# ATEM_GPI-Tally_Breakout_Board.net
KiCad netlist of a schematic drawn in EAGLE
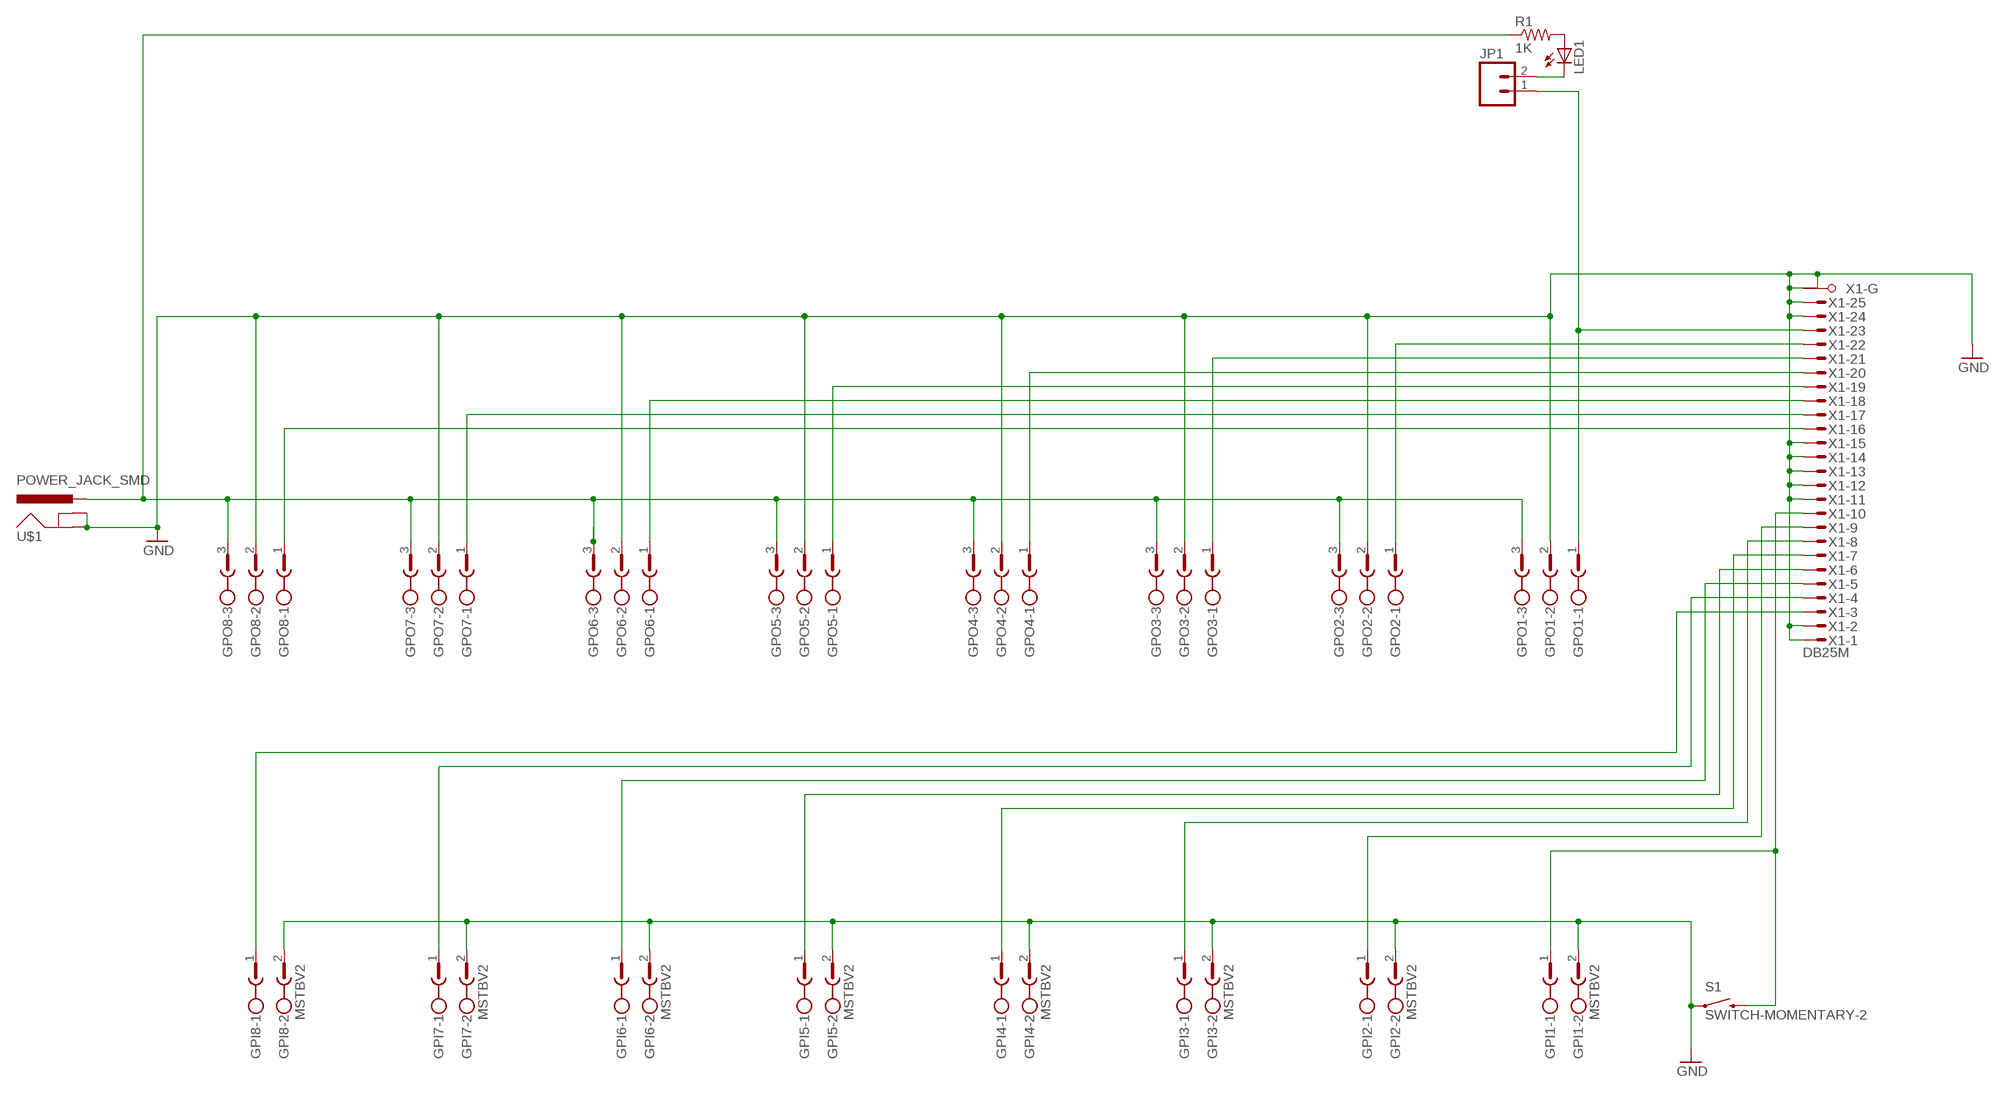
[diagram p0: schematic, sheet 1]

(export (version "E")
  (design (tool "Eeschema 10.0.6"))
  (components
    (comp (ref "GPI1")
      (value "MSTBV2")
      (footprint "eagle-import:MSTBV2")
      (fields
        (field (name "MPN") "MSTBV 2,5/2-GF-5.08")
        (field (name "MPN_1") "MSTBV 2,5/2-GF-5.08")
        (field (name "OC_FARNELL") "1792792")
        (field (name "OC_NEWARK") "69R9845")
      )
      (libsource (lib "eagle-import") (part "MSTBV2"))
    )
    (comp (ref "GPI2")
      (value "MSTBV2")
      (footprint "eagle-import:MSTBV2")
      (fields
        (field (name "MPN") "MSTBV 2,5/2-GF-5.08")
        (field (name "MPN_1") "MSTBV 2,5/2-GF-5.08")
        (field (name "OC_FARNELL") "1792792")
        (field (name "OC_NEWARK") "69R9845")
      )
      (libsource (lib "eagle-import") (part "MSTBV2"))
    )
    (comp (ref "GPI3")
      (value "MSTBV2")
      (footprint "eagle-import:MSTBV2")
      (fields
        (field (name "MPN") "MSTBV 2,5/2-GF-5.08")
        (field (name "MPN_1") "MSTBV 2,5/2-GF-5.08")
        (field (name "OC_FARNELL") "1792792")
        (field (name "OC_NEWARK") "69R9845")
      )
      (libsource (lib "eagle-import") (part "MSTBV2"))
    )
    (comp (ref "GPI4")
      (value "MSTBV2")
      (footprint "eagle-import:MSTBV2")
      (fields
        (field (name "MPN") "MSTBV 2,5/2-GF-5.08")
        (field (name "MPN_1") "MSTBV 2,5/2-GF-5.08")
        (field (name "OC_FARNELL") "1792792")
        (field (name "OC_NEWARK") "69R9845")
      )
      (libsource (lib "eagle-import") (part "MSTBV2"))
    )
    (comp (ref "GPI5")
      (value "MSTBV2")
      (footprint "eagle-import:MSTBV2")
      (fields
        (field (name "MPN") "MSTBV 2,5/2-GF-5.08")
        (field (name "MPN_1") "MSTBV 2,5/2-GF-5.08")
        (field (name "OC_FARNELL") "1792792")
        (field (name "OC_NEWARK") "69R9845")
      )
      (libsource (lib "eagle-import") (part "MSTBV2"))
    )
    (comp (ref "GPI6")
      (value "MSTBV2")
      (footprint "eagle-import:MSTBV2")
      (fields
        (field (name "MPN") "MSTBV 2,5/2-GF-5.08")
        (field (name "MPN_1") "MSTBV 2,5/2-GF-5.08")
        (field (name "OC_FARNELL") "1792792")
        (field (name "OC_NEWARK") "69R9845")
      )
      (libsource (lib "eagle-import") (part "MSTBV2"))
    )
    (comp (ref "GPI7")
      (value "MSTBV2")
      (footprint "eagle-import:MSTBV2")
      (fields
        (field (name "MPN") "MSTBV 2,5/2-GF-5.08")
        (field (name "MPN_1") "MSTBV 2,5/2-GF-5.08")
        (field (name "OC_FARNELL") "1792792")
        (field (name "OC_NEWARK") "69R9845")
      )
      (libsource (lib "eagle-import") (part "MSTBV2"))
    )
    (comp (ref "GPI8")
      (value "MSTBV2")
      (footprint "eagle-import:MSTBV2")
      (fields
        (field (name "MPN") "MSTBV 2,5/2-GF-5.08")
        (field (name "MPN_1") "MSTBV 2,5/2-GF-5.08")
        (field (name "OC_FARNELL") "1792792")
        (field (name "OC_NEWARK") "69R9845")
      )
      (libsource (lib "eagle-import") (part "MSTBV2"))
    )
    (comp (ref "GPO1")
      (value "CON1")
      (footprint "eagle-import:MSTBV3")
      (fields (field (name "MPN") "MSTBV 2,5/3-GF-5.08"))
      (libsource (lib "eagle-import") (part "MSTBV3"))
    )
    (comp (ref "GPO2")
      (value "CON1")
      (footprint "eagle-import:MSTBV3")
      (fields (field (name "MPN") "MSTBV 2,5/3-GF-5.08"))
      (libsource (lib "eagle-import") (part "MSTBV3"))
    )
    (comp (ref "GPO3")
      (value "CON1")
      (footprint "eagle-import:MSTBV3")
      (fields (field (name "MPN") "MSTBV 2,5/3-GF-5.08"))
      (libsource (lib "eagle-import") (part "MSTBV3"))
    )
    (comp (ref "GPO4")
      (value "CON1")
      (footprint "eagle-import:MSTBV3")
      (fields (field (name "MPN") "MSTBV 2,5/3-GF-5.08"))
      (libsource (lib "eagle-import") (part "MSTBV3"))
    )
    (comp (ref "GPO5")
      (value "CON1")
      (footprint "eagle-import:MSTBV3")
      (fields (field (name "MPN") "MSTBV 2,5/3-GF-5.08"))
      (libsource (lib "eagle-import") (part "MSTBV3"))
    )
    (comp (ref "GPO6")
      (value "CON1")
      (footprint "eagle-import:MSTBV3")
      (fields (field (name "MPN") "MSTBV 2,5/3-GF-5.08"))
      (libsource (lib "eagle-import") (part "MSTBV3"))
    )
    (comp (ref "GPO7")
      (value "CON1")
      (footprint "eagle-import:MSTBV3")
      (fields (field (name "MPN") "MSTBV 2,5/3-GF-5.08"))
      (libsource (lib "eagle-import") (part "MSTBV3"))
    )
    (comp (ref "GPO8")
      (value "CON1")
      (footprint "eagle-import:MSTBV3")
      (fields (field (name "MPN") "MSTBV 2,5/3-GF-5.08"))
      (libsource (lib "eagle-import") (part "MSTBV3"))
    )
    (comp (ref "JP1")
      (value "M02LOCK")
      (footprint "eagle-import:1X02_LOCK")
      (libsource (lib "eagle-import") (part "M02LOCK"))
    )
    (comp (ref "LED1")
      (value "LED5MM")
      (footprint "eagle-import:LED5MM")
      (libsource (lib "eagle-import") (part "LED5MM"))
    )
    (comp (ref "R1")
      (value "1K")
      (footprint "eagle-import:AXIAL-0.4")
      (libsource (lib "eagle-import") (part "RESISTORPTH-1/4W"))
    )
    (comp (ref "S1")
      (value "SWITCH-MOMENTARY-2")
      (footprint "eagle-import:TACTILE_SWITCH_TALL")
      (libsource (lib "eagle-import") (part "SWITCH-MOMENTARY-2"))
    )
    (comp (ref "U$1")
      (value "POWER_JACK_SMD")
      (footprint "eagle-import:POWER_JACK_SMD")
      (libsource (lib "eagle-import") (part "POWER_JACK_SMD"))
    )
    (comp (ref "X1")
      (value "DB25M")
      (footprint "eagle-import:M25HP")
      (libsource (lib "eagle-import") (part "M25HPS"))
    )
  )
  (nets
    (net (code "1") (name "GND") (class "Default")
      (node (ref "GPI1") (pin "2") (pinfunction "1_2") (pintype "passive"))
      (node (ref "GPI2") (pin "2") (pinfunction "1_2") (pintype "passive"))
      (node (ref "GPI3") (pin "2") (pinfunction "1_2") (pintype "passive"))
      (node (ref "GPI4") (pin "2") (pinfunction "1_2") (pintype "passive"))
      (node (ref "GPI5") (pin "2") (pinfunction "1_2") (pintype "passive"))
      (node (ref "GPI6") (pin "2") (pinfunction "1_2") (pintype "passive"))
      (node (ref "GPI7") (pin "2") (pinfunction "1_2") (pintype "passive"))
      (node (ref "GPI8") (pin "2") (pinfunction "1_2") (pintype "passive"))
      (node (ref "GPO1") (pin "2") (pinfunction "1_2") (pintype "passive"))
      (node (ref "GPO2") (pin "2") (pinfunction "1_2") (pintype "passive"))
      (node (ref "GPO3") (pin "2") (pinfunction "1_2") (pintype "passive"))
      (node (ref "GPO4") (pin "2") (pinfunction "1_2") (pintype "passive"))
      (node (ref "GPO5") (pin "2") (pinfunction "1_2") (pintype "passive"))
      (node (ref "GPO6") (pin "2") (pinfunction "1_2") (pintype "passive"))
      (node (ref "GPO7") (pin "2") (pinfunction "1_2") (pintype "passive"))
      (node (ref "GPO8") (pin "2") (pinfunction "1_2") (pintype "passive"))
      (node (ref "S1") (pin "A2") (pinfunction "1_A2") (pintype "passive"))
      (node (ref "U$1") (pin "GND") (pinfunction "GND_GND") (pintype "bidirectional"))
      (node (ref "U$1") (pin "SHUNT") (pinfunction "GNDBREAK_SHUNT") (pintype "bidirectional"))
      (node (ref "X1") (pin "1") (pinfunction "M_1") (pintype "passive"))
      (node (ref "X1") (pin "11") (pinfunction "M_11") (pintype "passive"))
      (node (ref "X1") (pin "12") (pinfunction "M_12") (pintype "passive"))
      (node (ref "X1") (pin "13") (pinfunction "M_13") (pintype "passive"))
      (node (ref "X1") (pin "14") (pinfunction "M_14") (pintype "passive"))
      (node (ref "X1") (pin "15") (pinfunction "M_15") (pintype "passive"))
      (node (ref "X1") (pin "2") (pinfunction "M_2") (pintype "passive"))
      (node (ref "X1") (pin "24") (pinfunction "M_24") (pintype "passive"))
      (node (ref "X1") (pin "25") (pinfunction "M_25") (pintype "passive"))
      (node (ref "X1") (pin "G1") (pinfunction "G1_G1") (pintype "passive"))
      (node (ref "X1") (pin "G2") (pinfunction "G2_G2") (pintype "passive"))
    )
    (net (code "2") (name "Net-(GPO1C-1)") (class "Default")
      (node (ref "GPO1") (pin "3") (pinfunction "1_3") (pintype "passive"))
      (node (ref "GPO2") (pin "3") (pinfunction "1_3") (pintype "passive"))
      (node (ref "GPO3") (pin "3") (pinfunction "1_3") (pintype "passive"))
      (node (ref "GPO4") (pin "3") (pinfunction "1_3") (pintype "passive"))
      (node (ref "GPO5") (pin "3") (pinfunction "1_3") (pintype "passive"))
      (node (ref "GPO6") (pin "3") (pinfunction "1_3") (pintype "passive"))
      (node (ref "GPO7") (pin "3") (pinfunction "1_3") (pintype "passive"))
      (node (ref "GPO8") (pin "3") (pinfunction "1_3") (pintype "passive"))
      (node (ref "R1") (pin "P$1") (pinfunction "1_P$1") (pintype "passive"))
      (node (ref "U$1") (pin "PWR") (pinfunction "PWR_PWR") (pintype "bidirectional"))
    )
    (net (code "3") (name "Net-(LED1-C)") (class "Default")
      (node (ref "JP1") (pin "2") (pinfunction "2_2") (pintype "passive"))
      (node (ref "LED1") (pin "K") (pinfunction "C_K") (pintype "passive"))
    )
    (net (code "4") (name "Net-(R1-2)") (class "Default")
      (node (ref "LED1") (pin "A") (pinfunction "A_A") (pintype "passive"))
      (node (ref "R1") (pin "P$2") (pinfunction "2_P$2") (pintype "passive"))
    )
    (net (code "5") (name "Net-(S1-2)") (class "Default")
      (node (ref "GPI1") (pin "1") (pinfunction "1_1") (pintype "passive"))
      (node (ref "S1") (pin "B2") (pinfunction "2_B2") (pintype "passive"))
      (node (ref "X1") (pin "10") (pinfunction "M_10") (pintype "passive"))
    )
    (net (code "6") (name "Net-(X1H-M)") (class "Default")
      (node (ref "GPO8") (pin "1") (pinfunction "1_1") (pintype "passive"))
      (node (ref "X1") (pin "16") (pinfunction "M_16") (pintype "passive"))
    )
    (net (code "7") (name "Net-(X1I-M)") (class "Default")
      (node (ref "GPO7") (pin "1") (pinfunction "1_1") (pintype "passive"))
      (node (ref "X1") (pin "17") (pinfunction "M_17") (pintype "passive"))
    )
    (net (code "8") (name "Net-(X1J-M)") (class "Default")
      (node (ref "GPO6") (pin "1") (pinfunction "1_1") (pintype "passive"))
      (node (ref "X1") (pin "18") (pinfunction "M_18") (pintype "passive"))
    )
    (net (code "9") (name "Net-(X1K-M)") (class "Default")
      (node (ref "GPO5") (pin "1") (pinfunction "1_1") (pintype "passive"))
      (node (ref "X1") (pin "19") (pinfunction "M_19") (pintype "passive"))
    )
    (net (code "10") (name "Net-(X1M-M)") (class "Default")
      (node (ref "GPO4") (pin "1") (pinfunction "1_1") (pintype "passive"))
      (node (ref "X1") (pin "20") (pinfunction "M_20") (pintype "passive"))
    )
    (net (code "11") (name "Net-(X1N-M)") (class "Default")
      (node (ref "GPO3") (pin "1") (pinfunction "1_1") (pintype "passive"))
      (node (ref "X1") (pin "21") (pinfunction "M_21") (pintype "passive"))
    )
    (net (code "12") (name "Net-(X1O-M)") (class "Default")
      (node (ref "GPO2") (pin "1") (pinfunction "1_1") (pintype "passive"))
      (node (ref "X1") (pin "22") (pinfunction "M_22") (pintype "passive"))
    )
    (net (code "13") (name "Net-(X1P-M)") (class "Default")
      (node (ref "GPO1") (pin "1") (pinfunction "1_1") (pintype "passive"))
      (node (ref "JP1") (pin "1") (pinfunction "1_1") (pintype "passive"))
      (node (ref "X1") (pin "23") (pinfunction "M_23") (pintype "passive"))
    )
    (net (code "14") (name "Net-(X1S-M)") (class "Default")
      (node (ref "GPI8") (pin "1") (pinfunction "1_1") (pintype "passive"))
      (node (ref "X1") (pin "3") (pinfunction "M_3") (pintype "passive"))
    )
    (net (code "15") (name "Net-(X1T-M)") (class "Default")
      (node (ref "GPI7") (pin "1") (pinfunction "1_1") (pintype "passive"))
      (node (ref "X1") (pin "4") (pinfunction "M_4") (pintype "passive"))
    )
    (net (code "16") (name "Net-(X1U-M)") (class "Default")
      (node (ref "GPI6") (pin "1") (pinfunction "1_1") (pintype "passive"))
      (node (ref "X1") (pin "5") (pinfunction "M_5") (pintype "passive"))
    )
    (net (code "17") (name "Net-(X1V-M)") (class "Default")
      (node (ref "GPI5") (pin "1") (pinfunction "1_1") (pintype "passive"))
      (node (ref "X1") (pin "6") (pinfunction "M_6") (pintype "passive"))
    )
    (net (code "18") (name "Net-(X1W-M)") (class "Default")
      (node (ref "GPI4") (pin "1") (pinfunction "1_1") (pintype "passive"))
      (node (ref "X1") (pin "7") (pinfunction "M_7") (pintype "passive"))
    )
    (net (code "19") (name "Net-(X1X-M)") (class "Default")
      (node (ref "GPI3") (pin "1") (pinfunction "1_1") (pintype "passive"))
      (node (ref "X1") (pin "8") (pinfunction "M_8") (pintype "passive"))
    )
    (net (code "20") (name "Net-(X1Y-M)") (class "Default")
      (node (ref "GPI2") (pin "1") (pinfunction "1_1") (pintype "passive"))
      (node (ref "X1") (pin "9") (pinfunction "M_9") (pintype "passive"))
    )
  )
)
